# Adafruit_MAX31865.net
KiCad netlist of a schematic drawn in EAGLE
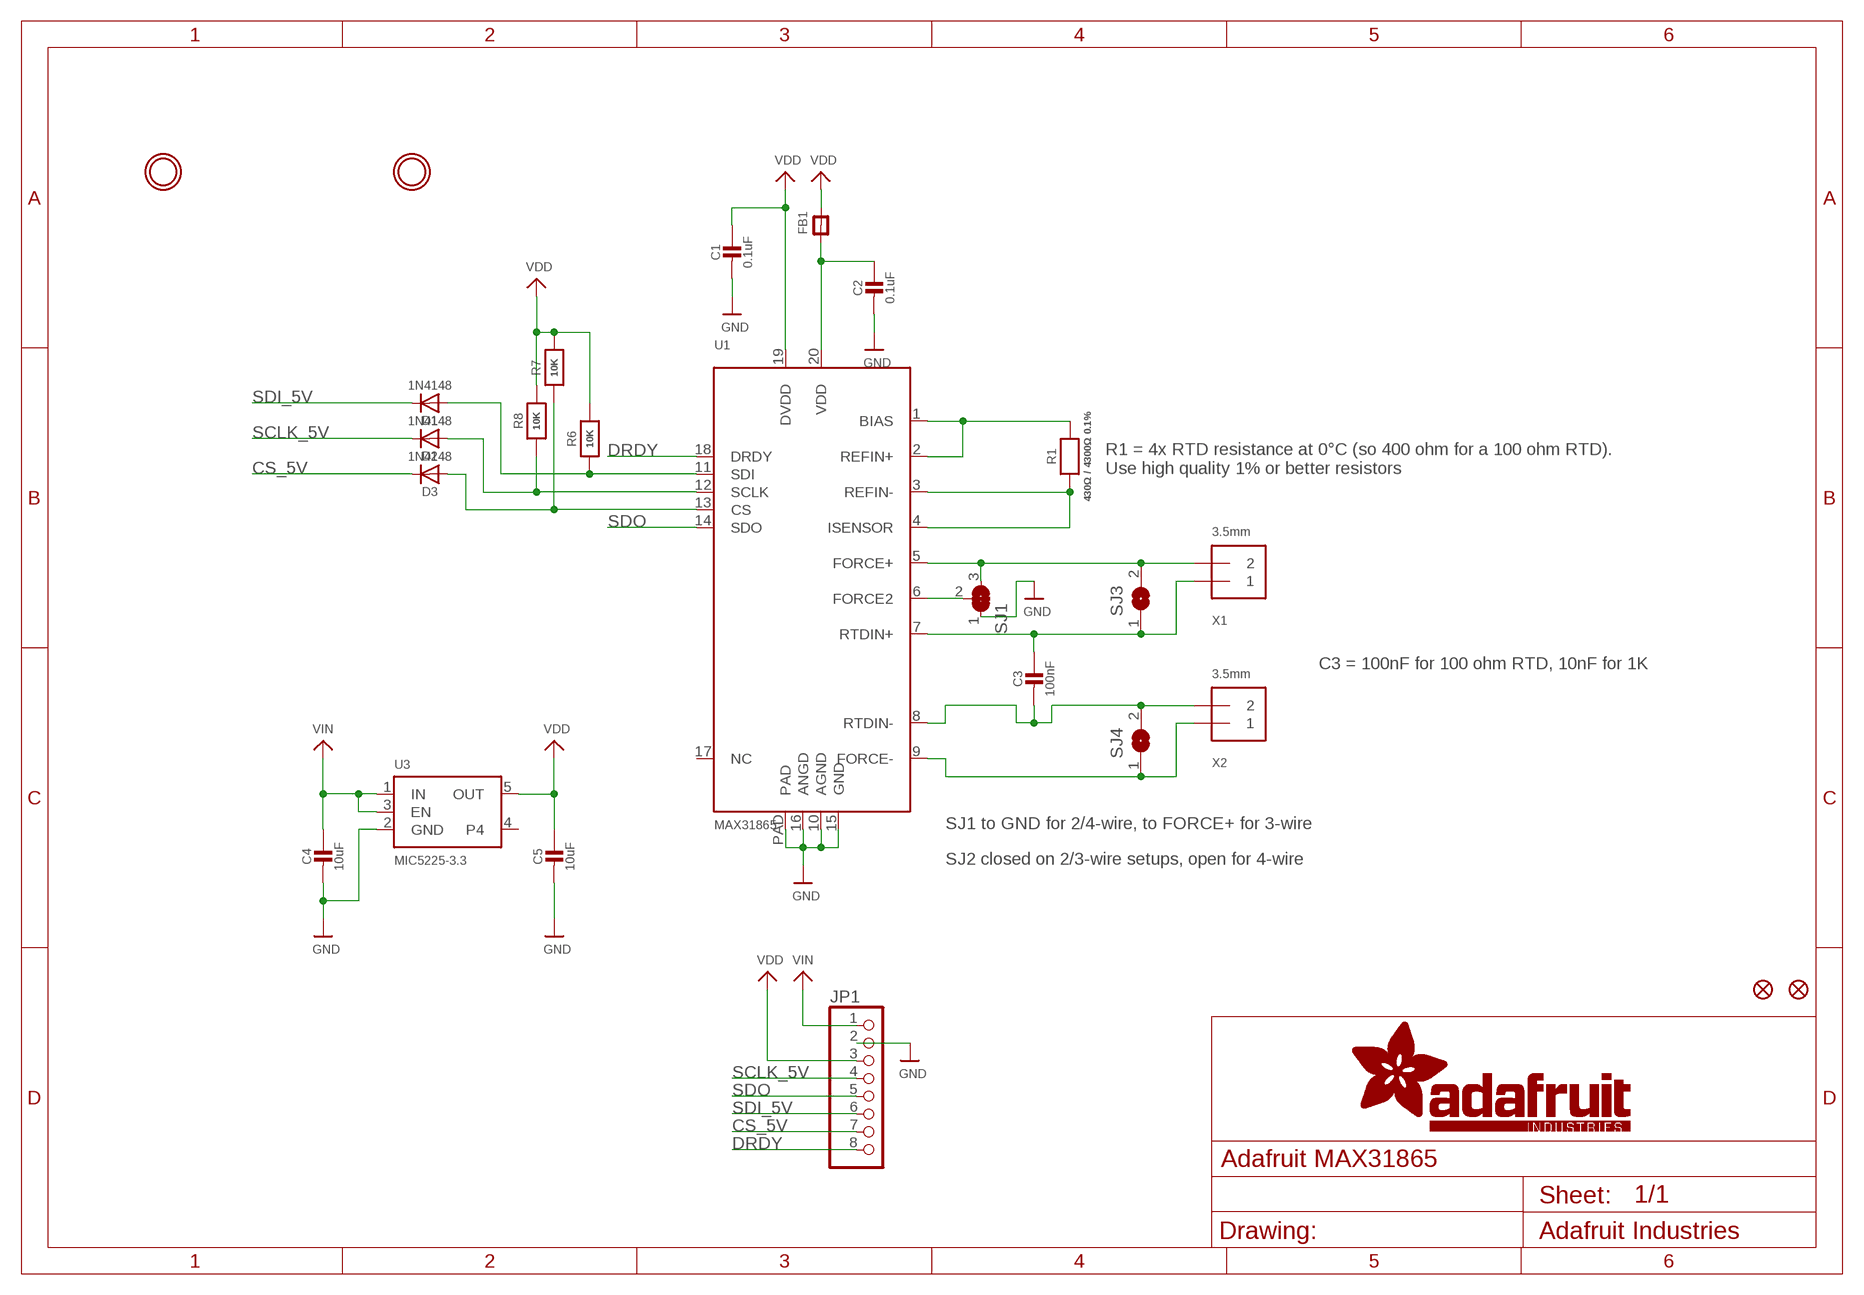
[diagram p0: schematic, sheet 1]

(export (version "E")
  (design (tool "Eeschema 10.0.6"))
  (components
    (comp (ref "C1")
      (value "0.1uF")
      (footprint "eagle-import:0805-NO")
      (libsource (lib "eagle-import") (part "CAP_CERAMIC0805-NOOUTLINE"))
    )
    (comp (ref "C2")
      (value "0.1uF")
      (footprint "eagle-import:0805-NO")
      (libsource (lib "eagle-import") (part "CAP_CERAMIC0805-NOOUTLINE"))
    )
    (comp (ref "C3")
      (value "100nF")
      (footprint "eagle-import:0805-NO")
      (libsource (lib "eagle-import") (part "CAP_CERAMIC0805-NOOUTLINE"))
    )
    (comp (ref "C4")
      (value "10uF")
      (footprint "eagle-import:0805-NO")
      (libsource (lib "eagle-import") (part "CAP_CERAMIC0805-NOOUTLINE"))
    )
    (comp (ref "C5")
      (value "10uF")
      (footprint "eagle-import:0805-NO")
      (libsource (lib "eagle-import") (part "CAP_CERAMIC0805-NOOUTLINE"))
    )
    (comp (ref "D1")
      (value "1N4148")
      (footprint "eagle-import:SOD-323")
      (libsource (lib "eagle-import") (part "DIODESOD-323"))
    )
    (comp (ref "D2")
      (value "1N4148")
      (footprint "eagle-import:SOD-323")
      (libsource (lib "eagle-import") (part "DIODESOD-323"))
    )
    (comp (ref "D3")
      (value "1N4148")
      (footprint "eagle-import:SOD-323")
      (libsource (lib "eagle-import") (part "DIODESOD-323"))
    )
    (comp (ref "FB1")
      (value "FERRITE-0805NO")
      (footprint "eagle-import:0805-NO")
      (libsource (lib "eagle-import") (part "FERRITE-0805NO"))
    )
    (comp (ref "FID1")
      (value "FIDUCIAL\"\"")
      (footprint "eagle-import:FIDUCIAL_1MM")
      (libsource (lib "eagle-import") (part "FIDUCIAL{dblquote}{dblquote}"))
    )
    (comp (ref "FID2")
      (value "FIDUCIAL\"\"")
      (footprint "eagle-import:FIDUCIAL_1MM")
      (libsource (lib "eagle-import") (part "FIDUCIAL{dblquote}{dblquote}"))
    )
    (comp (ref "JP1")
      (value "HEADER-1X870MIL")
      (footprint "eagle-import:1X08_ROUND_70")
      (libsource (lib "eagle-import") (part "HEADER-1X870MIL"))
    )
    (comp (ref "R1")
      (value "430Ω / 4300Ω 0.1%")
      (footprint "eagle-import:0805-NO")
      (libsource (lib "eagle-import") (part "RESISTOR0805_NOOUTLINE"))
    )
    (comp (ref "R6")
      (value "10K")
      (footprint "eagle-import:0805-NO")
      (libsource (lib "eagle-import") (part "RESISTOR0805_NOOUTLINE"))
    )
    (comp (ref "R7")
      (value "10K")
      (footprint "eagle-import:0805-NO")
      (libsource (lib "eagle-import") (part "RESISTOR0805_NOOUTLINE"))
    )
    (comp (ref "R8")
      (value "10K")
      (footprint "eagle-import:0805-NO")
      (libsource (lib "eagle-import") (part "RESISTOR0805_NOOUTLINE"))
    )
    (comp (ref "SJ1")
      (value "SOLDERJUMPER_2WAY")
      (footprint "eagle-import:SOLDERJUMPER_2WAY_OPEN_NOPASTE")
      (libsource (lib "eagle-import") (part "SOLDERJUMPER_2WAY"))
    )
    (comp (ref "SJ3")
      (value "SOLDERJUMPER")
      (footprint "eagle-import:SOLDERJUMPER_ARROW_NOPASTE")
      (libsource (lib "eagle-import") (part "SOLDERJUMPER"))
    )
    (comp (ref "SJ4")
      (value "SOLDERJUMPER")
      (footprint "eagle-import:SOLDERJUMPER_ARROW_NOPASTE")
      (libsource (lib "eagle-import") (part "SOLDERJUMPER"))
    )
    (comp (ref "U$18")
      (value "MOUNTINGHOLE2.5")
      (footprint "eagle-import:MOUNTINGHOLE_2.5_PLATED")
      (libsource (lib "eagle-import") (part "MOUNTINGHOLE2.5"))
    )
    (comp (ref "U$19")
      (value "MOUNTINGHOLE2.5")
      (footprint "eagle-import:MOUNTINGHOLE_2.5_PLATED")
      (libsource (lib "eagle-import") (part "MOUNTINGHOLE2.5"))
    )
    (comp (ref "U1")
      (value "MAX31865")
      (footprint "eagle-import:QFN20_4MM_0.65MM")
      (libsource (lib "eagle-import") (part "TEMP_MAX31865"))
    )
    (comp (ref "U3")
      (value "MIC5225-3.3")
      (footprint "eagle-import:SOT23-5")
      (libsource (lib "eagle-import") (part "VREG_SOT23-5"))
    )
    (comp (ref "X1")
      (value "3.5mm")
      (footprint "eagle-import:TERMBLOCK_1X2-3.5MM")
      (libsource (lib "eagle-import") (part "TERMBLOCK_1X2"))
    )
    (comp (ref "X2")
      (value "3.5mm")
      (footprint "eagle-import:TERMBLOCK_1X2-3.5MM")
      (libsource (lib "eagle-import") (part "TERMBLOCK_1X2"))
    )
  )
  (nets
    (net (code "1") (name "/CS_5V") (class "Default")
      (node (ref "D3") (pin "C") (pinfunction "C_C") (pintype "passive"))
      (node (ref "JP1") (pin "7") (pinfunction "7_7") (pintype "passive"))
    )
    (net (code "2") (name "/DRDY") (class "Default")
      (node (ref "JP1") (pin "8") (pinfunction "8_8") (pintype "passive"))
      (node (ref "U1") (pin "18") (pinfunction "DRDY_18") (pintype "output"))
    )
    (net (code "3") (name "/SCLK_5V") (class "Default")
      (node (ref "D2") (pin "C") (pinfunction "C_C") (pintype "passive"))
      (node (ref "JP1") (pin "4") (pinfunction "4_4") (pintype "passive"))
    )
    (net (code "4") (name "/SDI_5V") (class "Default")
      (node (ref "D1") (pin "C") (pinfunction "C_C") (pintype "passive"))
      (node (ref "JP1") (pin "6") (pinfunction "6_6") (pintype "passive"))
    )
    (net (code "5") (name "/SDO") (class "Default")
      (node (ref "JP1") (pin "5") (pinfunction "5_5") (pintype "passive"))
      (node (ref "U1") (pin "14") (pinfunction "SDO_14") (pintype "output"))
    )
    (net (code "6") (name "GND") (class "Default")
      (node (ref "C1") (pin "2") (pinfunction "2_2") (pintype "passive"))
      (node (ref "C2") (pin "2") (pinfunction "2_2") (pintype "passive"))
      (node (ref "C4") (pin "2") (pinfunction "2_2") (pintype "passive"))
      (node (ref "C5") (pin "2") (pinfunction "2_2") (pintype "passive"))
      (node (ref "JP1") (pin "2") (pinfunction "2_2") (pintype "passive"))
      (node (ref "SJ1") (pin "1") (pinfunction "1_1") (pintype "passive"))
      (node (ref "U1") (pin "10") (pinfunction "AGND_10") (pintype "power_in"))
      (node (ref "U1") (pin "15") (pinfunction "GND_15") (pintype "power_in"))
      (node (ref "U1") (pin "16") (pinfunction "ANGD_16") (pintype "power_in"))
      (node (ref "U1") (pin "PAD") (pinfunction "PAD_PAD") (pintype "power_in"))
      (node (ref "U3") (pin "2") (pinfunction "GND_2") (pintype "power_in"))
    )
    (net (code "7") (name "Net-(FB1-P$1)") (class "Default")
      (node (ref "C2") (pin "1") (pinfunction "1_1") (pintype "passive"))
      (node (ref "FB1") (pin "1") (pinfunction "P$1_1") (pintype "passive"))
      (node (ref "U1") (pin "20") (pinfunction "VDD_20") (pintype "power_in"))
    )
    (net (code "8") (name "Net-(U1-BIAS)") (class "Default")
      (node (ref "R1") (pin "2") (pinfunction "2_2") (pintype "passive"))
      (node (ref "U1") (pin "1") (pinfunction "BIAS_1") (pintype "output"))
      (node (ref "U1") (pin "2") (pinfunction "REFIN+_2") (pintype "bidirectional"))
    )
    (net (code "9") (name "Net-(U1-CS)") (class "Default")
      (node (ref "D3") (pin "A") (pinfunction "A_A") (pintype "passive"))
      (node (ref "R7") (pin "1") (pinfunction "1_1") (pintype "passive"))
      (node (ref "U1") (pin "13") (pinfunction "CS_13") (pintype "input"))
    )
    (net (code "10") (name "Net-(U1-FORCE+)") (class "Default")
      (node (ref "SJ1") (pin "3") (pinfunction "3_3") (pintype "passive"))
      (node (ref "SJ3") (pin "2") (pinfunction "2_2") (pintype "passive"))
      (node (ref "U1") (pin "5") (pinfunction "FORCE+_5") (pintype "output"))
      (node (ref "X1") (pin "2") (pinfunction "2_2") (pintype "passive"))
    )
    (net (code "11") (name "Net-(U1-FORCE-)") (class "Default")
      (node (ref "SJ4") (pin "1") (pinfunction "1_1") (pintype "passive"))
      (node (ref "U1") (pin "9") (pinfunction "FORCE-_9") (pintype "input"))
      (node (ref "X2") (pin "1") (pinfunction "1_1") (pintype "passive"))
    )
    (net (code "12") (name "Net-(U1-FORCE2)") (class "Default")
      (node (ref "SJ1") (pin "2") (pinfunction "2_2") (pintype "passive"))
      (node (ref "U1") (pin "6") (pinfunction "FORCE2_6") (pintype "bidirectional"))
    )
    (net (code "13") (name "Net-(U1-ISENSOR)") (class "Default")
      (node (ref "R1") (pin "1") (pinfunction "1_1") (pintype "passive"))
      (node (ref "U1") (pin "3") (pinfunction "REFIN-_3") (pintype "bidirectional"))
      (node (ref "U1") (pin "4") (pinfunction "ISENSOR_4") (pintype "input"))
    )
    (net (code "14") (name "Net-(U1-RTDIN+)") (class "Default")
      (node (ref "C3") (pin "1") (pinfunction "1_1") (pintype "passive"))
      (node (ref "SJ3") (pin "1") (pinfunction "1_1") (pintype "passive"))
      (node (ref "U1") (pin "7") (pinfunction "RTDIN+_7") (pintype "bidirectional"))
      (node (ref "X1") (pin "1") (pinfunction "1_1") (pintype "passive"))
    )
    (net (code "15") (name "Net-(U1-RTDIN-)") (class "Default")
      (node (ref "C3") (pin "2") (pinfunction "2_2") (pintype "passive"))
      (node (ref "SJ4") (pin "2") (pinfunction "2_2") (pintype "passive"))
      (node (ref "U1") (pin "8") (pinfunction "RTDIN-_8") (pintype "bidirectional"))
      (node (ref "X2") (pin "2") (pinfunction "2_2") (pintype "passive"))
    )
    (net (code "16") (name "Net-(U1-SCLK)") (class "Default")
      (node (ref "D2") (pin "A") (pinfunction "A_A") (pintype "passive"))
      (node (ref "R8") (pin "1") (pinfunction "1_1") (pintype "passive"))
      (node (ref "U1") (pin "12") (pinfunction "SCLK_12") (pintype "input"))
    )
    (net (code "17") (name "Net-(U1-SDI)") (class "Default")
      (node (ref "D1") (pin "A") (pinfunction "A_A") (pintype "passive"))
      (node (ref "R6") (pin "1") (pinfunction "1_1") (pintype "passive"))
      (node (ref "U1") (pin "11") (pinfunction "SDI_11") (pintype "input"))
    )
    (net (code "18") (name "VDD") (class "Default")
      (node (ref "C1") (pin "1") (pinfunction "1_1") (pintype "passive"))
      (node (ref "C5") (pin "1") (pinfunction "1_1") (pintype "passive"))
      (node (ref "FB1") (pin "2") (pinfunction "P$2_2") (pintype "passive"))
      (node (ref "JP1") (pin "3") (pinfunction "3_3") (pintype "passive"))
      (node (ref "R6") (pin "2") (pinfunction "2_2") (pintype "passive"))
      (node (ref "R7") (pin "2") (pinfunction "2_2") (pintype "passive"))
      (node (ref "R8") (pin "2") (pinfunction "2_2") (pintype "passive"))
      (node (ref "U1") (pin "19") (pinfunction "DVDD_19") (pintype "power_in"))
      (node (ref "U3") (pin "5") (pinfunction "OUT_5") (pintype "power_in"))
    )
    (net (code "19") (name "VIN") (class "Default")
      (node (ref "C4") (pin "1") (pinfunction "1_1") (pintype "passive"))
      (node (ref "JP1") (pin "1") (pinfunction "1_1") (pintype "passive"))
      (node (ref "U3") (pin "1") (pinfunction "IN_1") (pintype "power_in"))
      (node (ref "U3") (pin "3") (pinfunction "EN_3") (pintype "input"))
    )
    (net (code "20") (name "unconnected-(U1-NC-Pad17)") (class "Default")
      (node (ref "U1") (pin "17") (pinfunction "NC_17") (pintype "no_connect"))
    )
    (net (code "21") (name "unconnected-(U3-P4-Pad4)") (class "Default")
      (node (ref "U3") (pin "4") (pinfunction "P4_4") (pintype "bidirectional"))
    )
  )
)
